# actionneur.net
KiCad netlist of a schematic drawn in Altium Designer
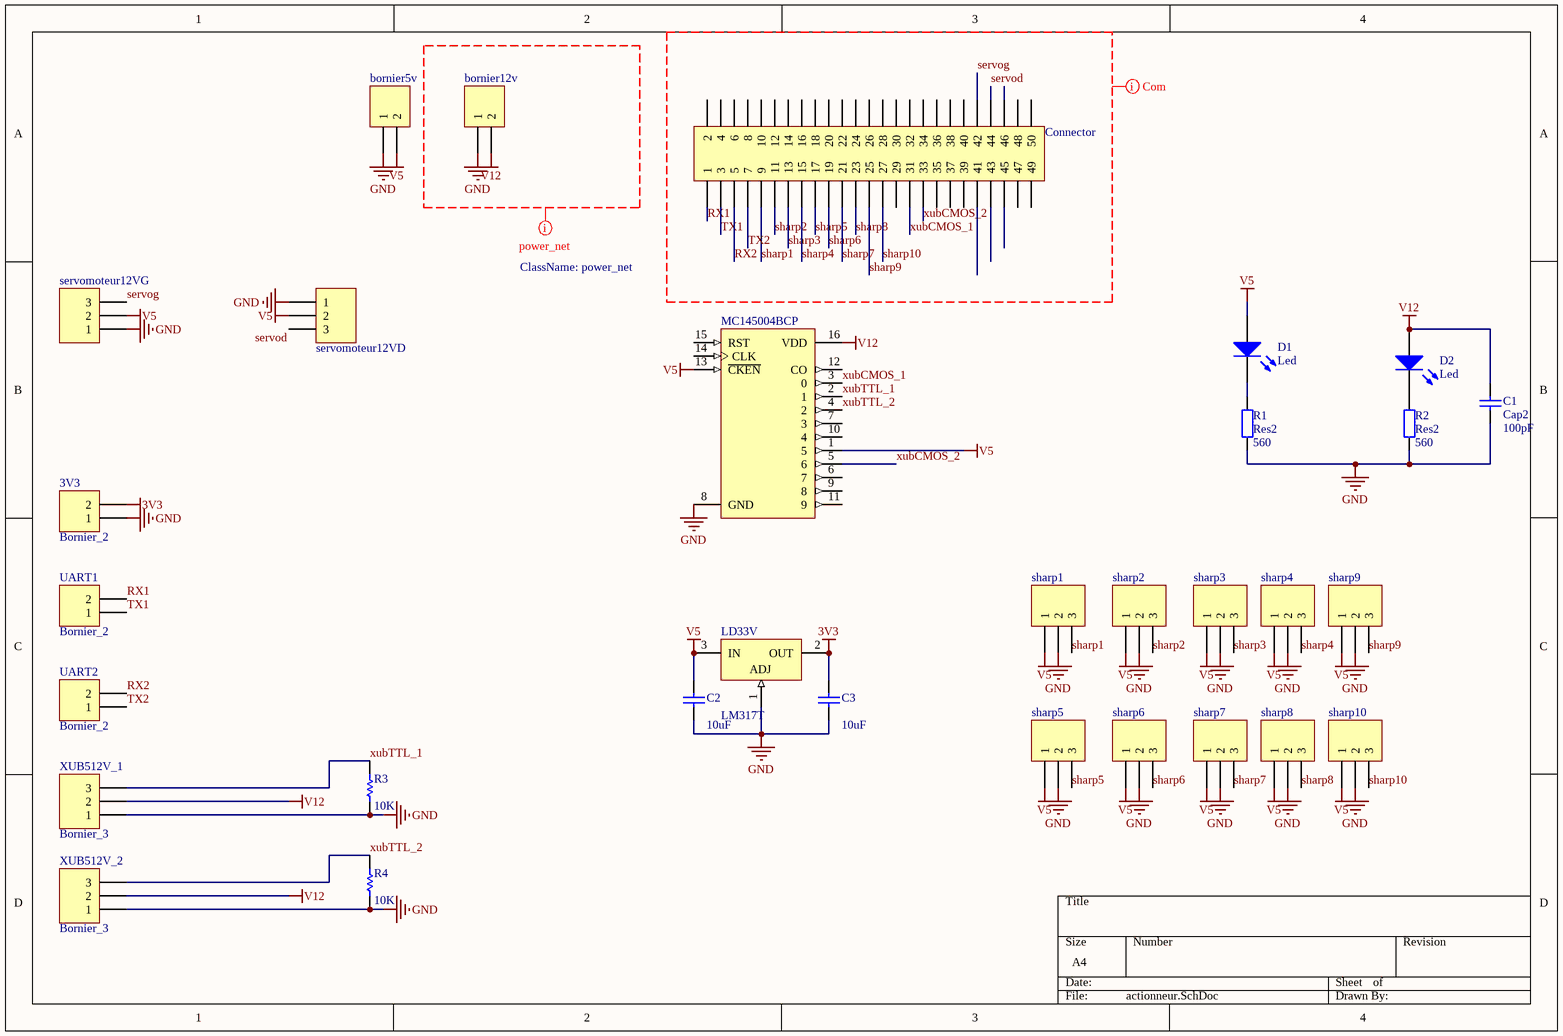
[diagram p0: actionneur.SchDoc]

(export (version "E")
  (design (tool "Eeschema 10.0.6"))
  (components
    (comp (ref "3V3")
      (value "Bornier_2")
      (footprint "Bornier_2")
      (description "Header, 2-Pin")
      (fields (field (name "PUBLISHER") "Altium Limited"))
      (libsource (lib "") (part "Bornier_2_1"))
    )
    (comp (ref "bornier5v")
      (value "Bornier_2")
      (footprint "Bornier_2")
      (description "Header, 2-Pin")
      (fields (field (name "PUBLISHER") "Altium Limited"))
      (libsource (lib "INTEGRATED_LIBRARY1_CONNECTEURS") (part "Bornier_2"))
    )
    (comp (ref "bornier12v")
      (value "Bornier_2")
      (footprint "Bornier_2")
      (description "Header, 2-Pin")
      (fields (field (name "PUBLISHER") "Altium Limited"))
      (libsource (lib "INTEGRATED_LIBRARY1_CONNECTEURS") (part "Bornier_2"))
    )
    (comp (ref "C1")
      (value "Cap2")
      (footprint "CAPA2")
      (description "Capacitor")
      (fields (field (name "ALTIUM_VALUE") "100pF") (field (name "PUBLISHER") "Altium Limited"))
      (libsource (lib "LIBRAIRIE_INTEGREE_PHELMA1") (part "Cap2"))
    )
    (comp (ref "C2")
      (value "10uF")
      (footprint "CAPA2")
      (description "Capacitor (Semiconductor SIM Model)")
      (fields (field (name "Comment") "Cap Semi") (field (name "PUBLISHER") "Altium Limited"))
      (libsource (lib "Miscellaneous Devices") (part "Cap Semi"))
    )
    (comp (ref "C3")
      (value "10uF")
      (footprint "CAPA2")
      (description "Capacitor (Semiconductor SIM Model)")
      (fields (field (name "Comment") "Cap Semi") (field (name "PUBLISHER") "Altium Limited"))
      (libsource (lib "Miscellaneous Devices") (part "Cap Semi"))
    )
    (comp (ref "Connector")
      (value "Header 25X2")
      (footprint "HDR2X25")
      (description "Header, 25-Pin, Dual row")
      (fields (field (name "PUBLISHER") "Altium Limited"))
      (libsource (lib "Miscellaneous Connectors") (part "Header 25X2"))
    )
    (comp (ref "D1")
      (value "Led")
      (footprint "LED")
      (description "LED")
      (fields (field (name "PUBLISHER") "Altium Limited"))
      (libsource (lib "LIBRAIRIE_INTEGREE_PHELMA1") (part "Led"))
    )
    (comp (ref "D2")
      (value "Led")
      (footprint "LED")
      (description "LED")
      (fields (field (name "PUBLISHER") "Altium Limited"))
      (libsource (lib "LIBRAIRIE_INTEGREE_PHELMA1") (part "Led"))
    )
    (comp (ref "LD33V")
      (value "LM317T")
      (footprint "TO220")
      (description "3-Terminal Adjustable Regulator")
      (fields (field (name "PUBLISHER") "Altium Limited"))
      (libsource (lib "LIBRAIRIE_INTEGREE_PHELMA1") (part "LM317T"))
    )
    (comp (ref "MC145004BCP")
      (value "CD4017BCN")
      (footprint "DIP16")
      (description "Decade Counter/Divider with 10 Decoded Outputs")
      (fields (field (name "PUBLISHER") "Altium Limited"))
      (libsource (lib "LIBRAIRIE_INTEGREE_PHELMA1") (part "CD4017BCN"))
    )
    (comp (ref "R1")
      (value "Res2")
      (footprint "res5_1/4W")
      (description "Resistor")
      (fields (field (name "ALTIUM_VALUE") "560") (field (name "PUBLISHER") "Altium Limited"))
      (libsource (lib "LIBRAIRIE_INTEGREE_PHELMA1") (part "Res2"))
    )
    (comp (ref "R2")
      (value "Res2")
      (footprint "res5_1/4W")
      (description "Resistor")
      (fields (field (name "ALTIUM_VALUE") "560") (field (name "PUBLISHER") "Altium Limited"))
      (libsource (lib "LIBRAIRIE_INTEGREE_PHELMA1") (part "Res2"))
    )
    (comp (ref "R3")
      (value "10K")
      (footprint "AXIAL-0.5")
      (description "Semiconductor Resistor")
      (fields (field (name "Comment") "Res Semi") (field (name "PUBLISHER") "Altium Limited"))
      (libsource (lib "Miscellaneous Devices") (part "Res Semi"))
    )
    (comp (ref "R4")
      (value "10K")
      (footprint "AXIAL-0.5")
      (description "Semiconductor Resistor")
      (fields (field (name "Comment") "Res Semi") (field (name "PUBLISHER") "Altium Limited"))
      (libsource (lib "Miscellaneous Devices") (part "Res Semi"))
    )
    (comp (ref "servomoteur12VD")
      (value "Bornier_3")
      (footprint "Bornier_3")
      (description "Header, 3-Pin")
      (fields (field (name "PUBLISHER") "Altium Limited"))
      (libsource (lib "") (part "Bornier_3_2"))
    )
    (comp (ref "servomoteur12VG")
      (value "Bornier_3")
      (footprint "Bornier_3")
      (description "Header, 3-Pin")
      (fields (field (name "PUBLISHER") "Altium Limited"))
      (libsource (lib "") (part "Bornier_3_1"))
    )
    (comp (ref "sharp1")
      (value "Bornier_3")
      (footprint "HDR1X3")
      (description "Header, 3-Pin")
      (fields (field (name "PUBLISHER") "Altium Limited"))
      (libsource (lib "INTEGRATED_LIBRARY1_CONNECTEURS") (part "Bornier_3"))
    )
    (comp (ref "sharp2")
      (value "Bornier_3")
      (footprint "HDR1X3")
      (description "Header, 3-Pin")
      (fields (field (name "PUBLISHER") "Altium Limited"))
      (libsource (lib "INTEGRATED_LIBRARY1_CONNECTEURS") (part "Bornier_3"))
    )
    (comp (ref "sharp3")
      (value "Bornier_3")
      (footprint "HDR1X3")
      (description "Header, 3-Pin")
      (fields (field (name "PUBLISHER") "Altium Limited"))
      (libsource (lib "INTEGRATED_LIBRARY1_CONNECTEURS") (part "Bornier_3"))
    )
    (comp (ref "sharp4")
      (value "Bornier_3")
      (footprint "HDR1X3")
      (description "Header, 3-Pin")
      (fields (field (name "PUBLISHER") "Altium Limited"))
      (libsource (lib "INTEGRATED_LIBRARY1_CONNECTEURS") (part "Bornier_3"))
    )
    (comp (ref "sharp5")
      (value "Bornier_3")
      (footprint "HDR1X3")
      (description "Header, 3-Pin")
      (fields (field (name "PUBLISHER") "Altium Limited"))
      (libsource (lib "INTEGRATED_LIBRARY1_CONNECTEURS") (part "Bornier_3"))
    )
    (comp (ref "sharp6")
      (value "Bornier_3")
      (footprint "HDR1X3")
      (description "Header, 3-Pin")
      (fields (field (name "PUBLISHER") "Altium Limited"))
      (libsource (lib "INTEGRATED_LIBRARY1_CONNECTEURS") (part "Bornier_3"))
    )
    (comp (ref "sharp7")
      (value "Bornier_3")
      (footprint "HDR1X3")
      (description "Header, 3-Pin")
      (fields (field (name "PUBLISHER") "Altium Limited"))
      (libsource (lib "INTEGRATED_LIBRARY1_CONNECTEURS") (part "Bornier_3"))
    )
    (comp (ref "sharp8")
      (value "Bornier_3")
      (footprint "HDR1X3")
      (description "Header, 3-Pin")
      (fields (field (name "PUBLISHER") "Altium Limited"))
      (libsource (lib "INTEGRATED_LIBRARY1_CONNECTEURS") (part "Bornier_3"))
    )
    (comp (ref "sharp9")
      (value "Bornier_3")
      (footprint "HDR1X3")
      (description "Header, 3-Pin")
      (fields (field (name "PUBLISHER") "Altium Limited"))
      (libsource (lib "INTEGRATED_LIBRARY1_CONNECTEURS") (part "Bornier_3"))
    )
    (comp (ref "sharp10")
      (value "Bornier_3")
      (footprint "HDR1X3")
      (description "Header, 3-Pin")
      (fields (field (name "PUBLISHER") "Altium Limited"))
      (libsource (lib "INTEGRATED_LIBRARY1_CONNECTEURS") (part "Bornier_3"))
    )
    (comp (ref "UART1")
      (value "Bornier_2")
      (footprint "Bornier_2")
      (description "Header, 2-Pin")
      (fields (field (name "PUBLISHER") "Altium Limited"))
      (libsource (lib "") (part "Bornier_2_1"))
    )
    (comp (ref "UART2")
      (value "Bornier_2")
      (footprint "Bornier_2")
      (description "Header, 2-Pin")
      (fields (field (name "PUBLISHER") "Altium Limited"))
      (libsource (lib "") (part "Bornier_2_1"))
    )
    (comp (ref "XUB512V_1")
      (value "Bornier_3")
      (footprint "Bornier_3")
      (description "Header, 3-Pin")
      (fields (field (name "PUBLISHER") "Altium Limited"))
      (libsource (lib "") (part "Bornier_3_1"))
    )
    (comp (ref "XUB512V_2")
      (value "Bornier_3")
      (footprint "Bornier_3")
      (description "Header, 3-Pin")
      (fields (field (name "PUBLISHER") "Altium Limited"))
      (libsource (lib "") (part "Bornier_3_1"))
    )
  )
  (nets
    (net (code "1") (name "/RX1") (class "Default")
      (node (ref "Connector") (pin "1") (pinfunction "1_1") (pintype "passive"))
      (node (ref "UART1") (pin "2") (pinfunction "2_2") (pintype "passive"))
    )
    (net (code "2") (name "/RX2") (class "Default")
      (node (ref "Connector") (pin "5") (pinfunction "5_5") (pintype "passive"))
      (node (ref "UART2") (pin "2") (pinfunction "2_2") (pintype "passive"))
    )
    (net (code "3") (name "/TX1") (class "Default")
      (node (ref "Connector") (pin "3") (pinfunction "3_3") (pintype "passive"))
      (node (ref "UART1") (pin "1") (pinfunction "1_1") (pintype "passive"))
    )
    (net (code "4") (name "/TX2") (class "Default")
      (node (ref "Connector") (pin "7") (pinfunction "7_7") (pintype "passive"))
      (node (ref "UART2") (pin "1") (pinfunction "1_1") (pintype "passive"))
    )
    (net (code "5") (name "/servod") (class "Default")
      (node (ref "Connector") (pin "44") (pinfunction "44_44") (pintype "passive"))
      (node (ref "servomoteur12VD") (pin "3") (pinfunction "3_3") (pintype "passive"))
    )
    (net (code "6") (name "/servog") (class "Default")
      (node (ref "Connector") (pin "42") (pinfunction "42_42") (pintype "passive"))
      (node (ref "servomoteur12VG") (pin "3") (pinfunction "3_3") (pintype "passive"))
    )
    (net (code "7") (name "/sharp1") (class "Default")
      (node (ref "Connector") (pin "9") (pinfunction "9_9") (pintype "passive"))
      (node (ref "sharp1") (pin "3") (pinfunction "3_3") (pintype "passive"))
    )
    (net (code "8") (name "/sharp2") (class "Default")
      (node (ref "Connector") (pin "11") (pinfunction "11_11") (pintype "passive"))
      (node (ref "sharp2") (pin "3") (pinfunction "3_3") (pintype "passive"))
    )
    (net (code "9") (name "/sharp3") (class "Default")
      (node (ref "Connector") (pin "13") (pinfunction "13_13") (pintype "passive"))
      (node (ref "sharp3") (pin "3") (pinfunction "3_3") (pintype "passive"))
    )
    (net (code "10") (name "/sharp4") (class "Default")
      (node (ref "Connector") (pin "15") (pinfunction "15_15") (pintype "passive"))
      (node (ref "sharp4") (pin "3") (pinfunction "3_3") (pintype "passive"))
    )
    (net (code "11") (name "/sharp5") (class "Default")
      (node (ref "Connector") (pin "17") (pinfunction "17_17") (pintype "passive"))
      (node (ref "sharp5") (pin "3") (pinfunction "3_3") (pintype "passive"))
    )
    (net (code "12") (name "/sharp6") (class "Default")
      (node (ref "Connector") (pin "19") (pinfunction "19_19") (pintype "passive"))
      (node (ref "sharp6") (pin "3") (pinfunction "3_3") (pintype "passive"))
    )
    (net (code "13") (name "/sharp7") (class "Default")
      (node (ref "Connector") (pin "21") (pinfunction "21_21") (pintype "passive"))
      (node (ref "sharp7") (pin "3") (pinfunction "3_3") (pintype "passive"))
    )
    (net (code "14") (name "/sharp8") (class "Default")
      (node (ref "Connector") (pin "23") (pinfunction "23_23") (pintype "passive"))
      (node (ref "sharp8") (pin "3") (pinfunction "3_3") (pintype "passive"))
    )
    (net (code "15") (name "/sharp9") (class "Default")
      (node (ref "Connector") (pin "25") (pinfunction "25_25") (pintype "passive"))
      (node (ref "sharp9") (pin "3") (pinfunction "3_3") (pintype "passive"))
    )
    (net (code "16") (name "/sharp10") (class "Default")
      (node (ref "Connector") (pin "27") (pinfunction "27_27") (pintype "passive"))
      (node (ref "sharp10") (pin "3") (pinfunction "3_3") (pintype "passive"))
    )
    (net (code "17") (name "/xubCMOS_1") (class "Default")
      (node (ref "Connector") (pin "31") (pinfunction "31_31") (pintype "passive"))
      (node (ref "MC145004BCP") (pin "3") (pinfunction "0_3") (pintype "output"))
    )
    (net (code "18") (name "/xubCMOS_2") (class "Default")
      (node (ref "Connector") (pin "33") (pinfunction "33_33") (pintype "passive"))
      (node (ref "MC145004BCP") (pin "5") (pinfunction "6_5") (pintype "output"))
    )
    (net (code "19") (name "/xubTTL_1") (class "Default")
      (node (ref "MC145004BCP") (pin "2") (pinfunction "1_2") (pintype "output"))
      (node (ref "R3") (pin "2") (pinfunction "2_2") (pintype "passive"))
      (node (ref "XUB512V_1") (pin "3") (pinfunction "3_3") (pintype "passive"))
    )
    (net (code "20") (name "/xubTTL_2") (class "Default")
      (node (ref "MC145004BCP") (pin "4") (pinfunction "2_4") (pintype "output"))
      (node (ref "R4") (pin "2") (pinfunction "2_2") (pintype "passive"))
      (node (ref "XUB512V_2") (pin "3") (pinfunction "3_3") (pintype "passive"))
    )
    (net (code "21") (name "3V3") (class "Default")
      (node (ref "3V3") (pin "2") (pinfunction "2_2") (pintype "passive"))
      (node (ref "C3") (pin "2") (pinfunction "2_2") (pintype "passive"))
      (node (ref "LD33V") (pin "2") (pinfunction "OUT_2") (pintype "power_in"))
    )
    (net (code "22") (name "GND") (class "Default")
      (node (ref "3V3") (pin "1") (pinfunction "1_1") (pintype "passive"))
      (node (ref "C1") (pin "1") (pinfunction "1_1") (pintype "passive"))
      (node (ref "C2") (pin "1") (pinfunction "1_1") (pintype "passive"))
      (node (ref "C3") (pin "1") (pinfunction "1_1") (pintype "passive"))
      (node (ref "LD33V") (pin "1") (pinfunction "ADJ_1") (pintype "input"))
      (node (ref "MC145004BCP") (pin "8") (pinfunction "GND_8") (pintype "power_in"))
      (node (ref "R1") (pin "1") (pinfunction "1_1") (pintype "passive"))
      (node (ref "R2") (pin "1") (pinfunction "1_1") (pintype "passive"))
      (node (ref "R3") (pin "1") (pinfunction "1_1") (pintype "passive"))
      (node (ref "R4") (pin "1") (pinfunction "1_1") (pintype "passive"))
      (node (ref "XUB512V_1") (pin "1") (pinfunction "1_1") (pintype "passive"))
      (node (ref "XUB512V_2") (pin "1") (pinfunction "1_1") (pintype "passive"))
      (node (ref "bornier12v") (pin "1") (pinfunction "1_1") (pintype "passive"))
      (node (ref "bornier5v") (pin "1") (pinfunction "1_1") (pintype "passive"))
      (node (ref "servomoteur12VD") (pin "1") (pinfunction "1_1") (pintype "passive"))
      (node (ref "servomoteur12VG") (pin "1") (pinfunction "1_1") (pintype "passive"))
      (node (ref "sharp1") (pin "2") (pinfunction "2_2") (pintype "passive"))
      (node (ref "sharp10") (pin "2") (pinfunction "2_2") (pintype "passive"))
      (node (ref "sharp2") (pin "2") (pinfunction "2_2") (pintype "passive"))
      (node (ref "sharp3") (pin "2") (pinfunction "2_2") (pintype "passive"))
      (node (ref "sharp4") (pin "2") (pinfunction "2_2") (pintype "passive"))
      (node (ref "sharp5") (pin "2") (pinfunction "2_2") (pintype "passive"))
      (node (ref "sharp6") (pin "2") (pinfunction "2_2") (pintype "passive"))
      (node (ref "sharp7") (pin "2") (pinfunction "2_2") (pintype "passive"))
      (node (ref "sharp8") (pin "2") (pinfunction "2_2") (pintype "passive"))
      (node (ref "sharp9") (pin "2") (pinfunction "2_2") (pintype "passive"))
    )
    (net (code "23") (name "Net-(D1-K)") (class "Default")
      (node (ref "D1") (pin "2") (pinfunction "K_2") (pintype "passive"))
      (node (ref "R1") (pin "2") (pinfunction "2_2") (pintype "passive"))
    )
    (net (code "24") (name "Net-(D2-K)") (class "Default")
      (node (ref "D2") (pin "2") (pinfunction "K_2") (pintype "passive"))
      (node (ref "R2") (pin "2") (pinfunction "2_2") (pintype "passive"))
    )
    (net (code "25") (name "V5") (class "Default")
      (node (ref "C2") (pin "2") (pinfunction "2_2") (pintype "passive"))
      (node (ref "D1") (pin "1") (pinfunction "A_1") (pintype "passive"))
      (node (ref "LD33V") (pin "3") (pinfunction "IN_3") (pintype "power_in"))
      (node (ref "MC145004BCP") (pin "1") (pinfunction "5_1") (pintype "output"))
      (node (ref "MC145004BCP") (pin "13") (pinfunction "~{CKEN}_13") (pintype "input"))
      (node (ref "bornier5v") (pin "2") (pinfunction "2_2") (pintype "passive"))
      (node (ref "servomoteur12VD") (pin "2") (pinfunction "2_2") (pintype "passive"))
      (node (ref "servomoteur12VG") (pin "2") (pinfunction "2_2") (pintype "passive"))
      (node (ref "sharp1") (pin "1") (pinfunction "1_1") (pintype "passive"))
      (node (ref "sharp10") (pin "1") (pinfunction "1_1") (pintype "passive"))
      (node (ref "sharp2") (pin "1") (pinfunction "1_1") (pintype "passive"))
      (node (ref "sharp3") (pin "1") (pinfunction "1_1") (pintype "passive"))
      (node (ref "sharp4") (pin "1") (pinfunction "1_1") (pintype "passive"))
      (node (ref "sharp5") (pin "1") (pinfunction "1_1") (pintype "passive"))
      (node (ref "sharp6") (pin "1") (pinfunction "1_1") (pintype "passive"))
      (node (ref "sharp7") (pin "1") (pinfunction "1_1") (pintype "passive"))
      (node (ref "sharp8") (pin "1") (pinfunction "1_1") (pintype "passive"))
      (node (ref "sharp9") (pin "1") (pinfunction "1_1") (pintype "passive"))
    )
    (net (code "26") (name "V12") (class "Default")
      (node (ref "C1") (pin "2") (pinfunction "2_2") (pintype "passive"))
      (node (ref "D2") (pin "1") (pinfunction "A_1") (pintype "passive"))
      (node (ref "MC145004BCP") (pin "16") (pinfunction "VDD_16") (pintype "power_in"))
      (node (ref "XUB512V_1") (pin "2") (pinfunction "2_2") (pintype "passive"))
      (node (ref "XUB512V_2") (pin "2") (pinfunction "2_2") (pintype "passive"))
      (node (ref "bornier12v") (pin "2") (pinfunction "2_2") (pintype "passive"))
    )
    (net (code "27") (name "unconnected-(Connector-Pad2)") (class "Default")
      (node (ref "Connector") (pin "2") (pinfunction "2_2") (pintype "passive"))
    )
    (net (code "28") (name "unconnected-(Connector-Pad4)") (class "Default")
      (node (ref "Connector") (pin "4") (pinfunction "4_4") (pintype "passive"))
    )
    (net (code "29") (name "unconnected-(Connector-Pad6)") (class "Default")
      (node (ref "Connector") (pin "6") (pinfunction "6_6") (pintype "passive"))
    )
    (net (code "30") (name "unconnected-(Connector-Pad8)") (class "Default")
      (node (ref "Connector") (pin "8") (pinfunction "8_8") (pintype "passive"))
    )
    (net (code "31") (name "unconnected-(Connector-Pad10)") (class "Default")
      (node (ref "Connector") (pin "10") (pinfunction "10_10") (pintype "passive"))
    )
    (net (code "32") (name "unconnected-(Connector-Pad12)") (class "Default")
      (node (ref "Connector") (pin "12") (pinfunction "12_12") (pintype "passive"))
    )
    (net (code "33") (name "unconnected-(Connector-Pad14)") (class "Default")
      (node (ref "Connector") (pin "14") (pinfunction "14_14") (pintype "passive"))
    )
    (net (code "34") (name "unconnected-(Connector-Pad16)") (class "Default")
      (node (ref "Connector") (pin "16") (pinfunction "16_16") (pintype "passive"))
    )
    (net (code "35") (name "unconnected-(Connector-Pad18)") (class "Default")
      (node (ref "Connector") (pin "18") (pinfunction "18_18") (pintype "passive"))
    )
    (net (code "36") (name "unconnected-(Connector-Pad20)") (class "Default")
      (node (ref "Connector") (pin "20") (pinfunction "20_20") (pintype "passive"))
    )
    (net (code "37") (name "unconnected-(Connector-Pad22)") (class "Default")
      (node (ref "Connector") (pin "22") (pinfunction "22_22") (pintype "passive"))
    )
    (net (code "38") (name "unconnected-(Connector-Pad24)") (class "Default")
      (node (ref "Connector") (pin "24") (pinfunction "24_24") (pintype "passive"))
    )
    (net (code "39") (name "unconnected-(Connector-Pad26)") (class "Default")
      (node (ref "Connector") (pin "26") (pinfunction "26_26") (pintype "passive"))
    )
    (net (code "40") (name "unconnected-(Connector-Pad28)") (class "Default")
      (node (ref "Connector") (pin "28") (pinfunction "28_28") (pintype "passive"))
    )
    (net (code "41") (name "unconnected-(Connector-Pad29)") (class "Default")
      (node (ref "Connector") (pin "29") (pinfunction "29_29") (pintype "passive"))
    )
    (net (code "42") (name "unconnected-(Connector-Pad30)") (class "Default")
      (node (ref "Connector") (pin "30") (pinfunction "30_30") (pintype "passive"))
    )
    (net (code "43") (name "unconnected-(Connector-Pad32)") (class "Default")
      (node (ref "Connector") (pin "32") (pinfunction "32_32") (pintype "passive"))
    )
    (net (code "44") (name "unconnected-(Connector-Pad34)") (class "Default")
      (node (ref "Connector") (pin "34") (pinfunction "34_34") (pintype "passive"))
    )
    (net (code "45") (name "unconnected-(Connector-Pad35)") (class "Default")
      (node (ref "Connector") (pin "35") (pinfunction "35_35") (pintype "passive"))
    )
    (net (code "46") (name "unconnected-(Connector-Pad36)") (class "Default")
      (node (ref "Connector") (pin "36") (pinfunction "36_36") (pintype "passive"))
    )
    (net (code "47") (name "unconnected-(Connector-Pad37)") (class "Default")
      (node (ref "Connector") (pin "37") (pinfunction "37_37") (pintype "passive"))
    )
    (net (code "48") (name "unconnected-(Connector-Pad38)") (class "Default")
      (node (ref "Connector") (pin "38") (pinfunction "38_38") (pintype "passive"))
    )
    (net (code "49") (name "unconnected-(Connector-Pad39)") (class "Default")
      (node (ref "Connector") (pin "39") (pinfunction "39_39") (pintype "passive"))
    )
    (net (code "50") (name "unconnected-(Connector-Pad40)") (class "Default")
      (node (ref "Connector") (pin "40") (pinfunction "40_40") (pintype "passive"))
    )
    (net (code "51") (name "unconnected-(Connector-Pad41)") (class "Default")
      (node (ref "Connector") (pin "41") (pinfunction "41_41") (pintype "passive"))
    )
    (net (code "52") (name "unconnected-(Connector-Pad43)") (class "Default")
      (node (ref "Connector") (pin "43") (pinfunction "43_43") (pintype "passive"))
    )
    (net (code "53") (name "unconnected-(Connector-Pad45)") (class "Default")
      (node (ref "Connector") (pin "45") (pinfunction "45_45") (pintype "passive"))
    )
    (net (code "54") (name "unconnected-(Connector-Pad46)") (class "Default")
      (node (ref "Connector") (pin "46") (pinfunction "46_46") (pintype "passive"))
    )
    (net (code "55") (name "unconnected-(Connector-Pad47)") (class "Default")
      (node (ref "Connector") (pin "47") (pinfunction "47_47") (pintype "passive"))
    )
    (net (code "56") (name "unconnected-(Connector-Pad48)") (class "Default")
      (node (ref "Connector") (pin "48") (pinfunction "48_48") (pintype "passive"))
    )
    (net (code "57") (name "unconnected-(Connector-Pad49)") (class "Default")
      (node (ref "Connector") (pin "49") (pinfunction "49_49") (pintype "passive"))
    )
    (net (code "58") (name "unconnected-(Connector-Pad50)") (class "Default")
      (node (ref "Connector") (pin "50") (pinfunction "50_50") (pintype "passive"))
    )
    (net (code "59") (name "unconnected-(MC145004BCP-3-Pad7)") (class "Default")
      (node (ref "MC145004BCP") (pin "7") (pinfunction "3_7") (pintype "output"))
    )
    (net (code "60") (name "unconnected-(MC145004BCP-4-Pad10)") (class "Default")
      (node (ref "MC145004BCP") (pin "10") (pinfunction "4_10") (pintype "output"))
    )
    (net (code "61") (name "unconnected-(MC145004BCP-7-Pad6)") (class "Default")
      (node (ref "MC145004BCP") (pin "6") (pinfunction "7_6") (pintype "output"))
    )
    (net (code "62") (name "unconnected-(MC145004BCP-8-Pad9)") (class "Default")
      (node (ref "MC145004BCP") (pin "9") (pinfunction "8_9") (pintype "output"))
    )
    (net (code "63") (name "unconnected-(MC145004BCP-9-Pad11)") (class "Default")
      (node (ref "MC145004BCP") (pin "11") (pinfunction "9_11") (pintype "output"))
    )
    (net (code "64") (name "unconnected-(MC145004BCP-CLK-Pad14)") (class "Default")
      (node (ref "MC145004BCP") (pin "14") (pinfunction "CLK_14") (pintype "input"))
    )
    (net (code "65") (name "unconnected-(MC145004BCP-CO-Pad12)") (class "Default")
      (node (ref "MC145004BCP") (pin "12") (pinfunction "CO_12") (pintype "output"))
    )
    (net (code "66") (name "unconnected-(MC145004BCP-RST-Pad15)") (class "Default")
      (node (ref "MC145004BCP") (pin "15") (pinfunction "RST_15") (pintype "input"))
    )
  )
)
